# PhatStats_Slim_Enclosure_2_8_ILI9341_QTP.net
KiCad netlist of a schematic drawn in EAGLE
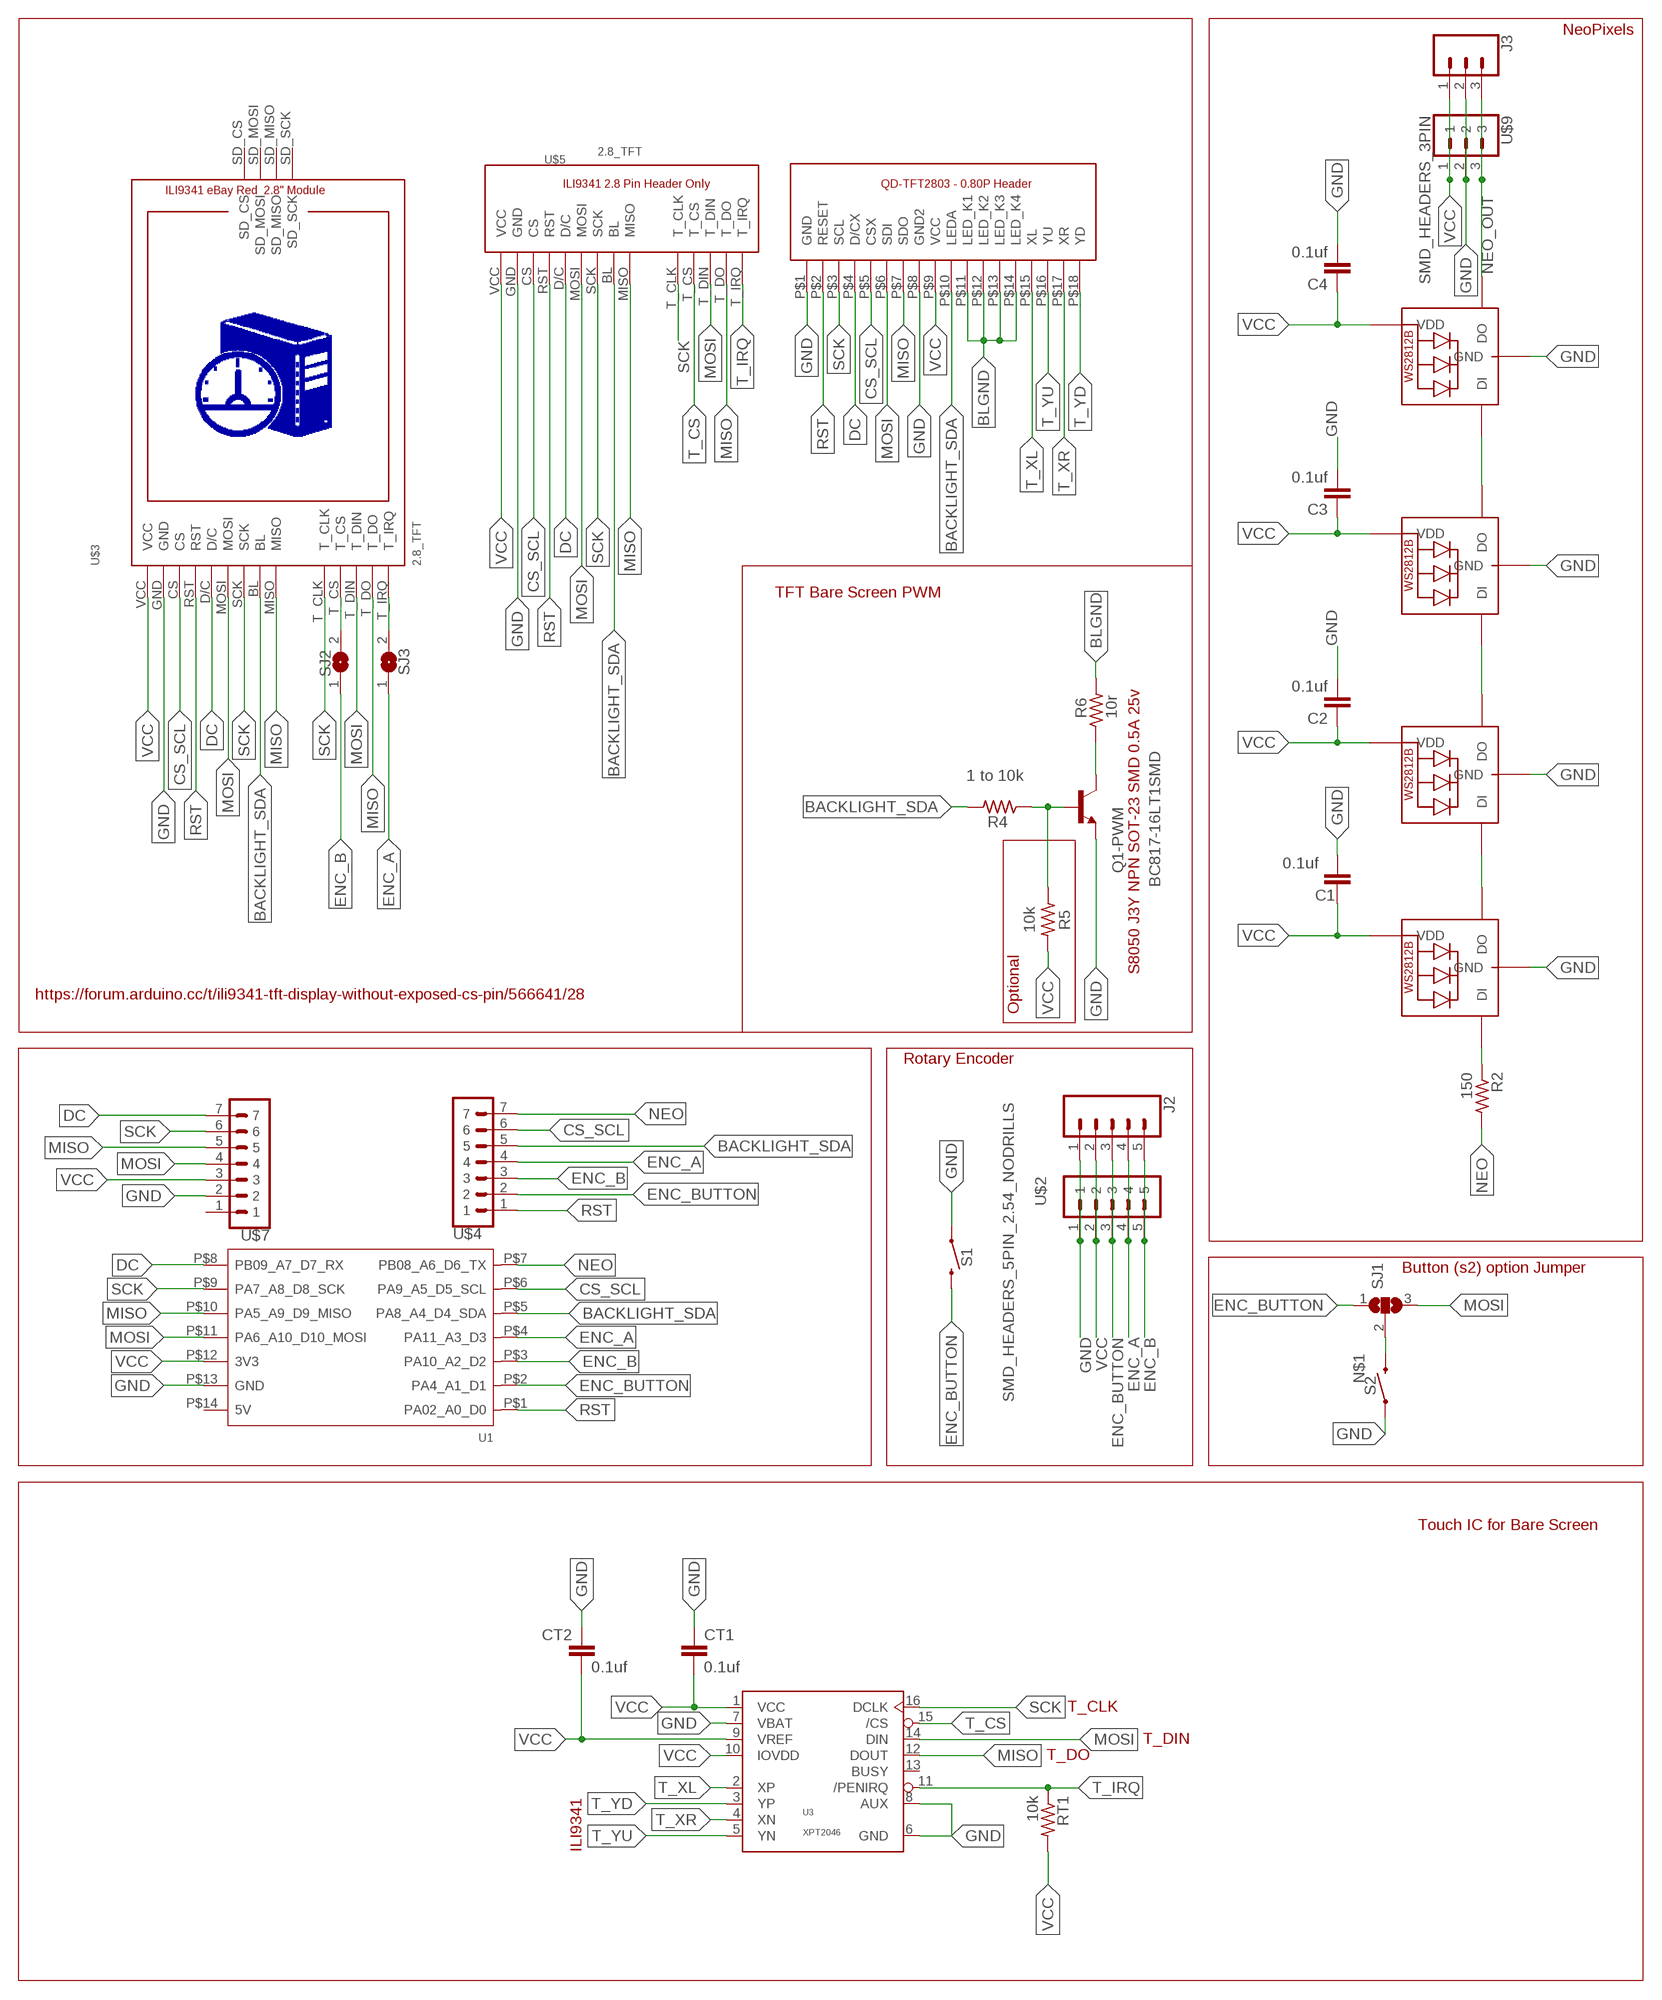
[diagram p0: schematic, sheet 1]

(export (version "E")
  (design (tool "Eeschema 10.0.6"))
  (components
    (comp (ref "0")
      (value "ILI9341-2.8")
      (footprint "eagle-import:ILI9341-2.8")
      (libsource (lib "eagle-import") (part "ILI9341-2.8"))
    )
    (comp (ref "C1")
      (value "0.1uf")
      (footprint "eagle-import:C1206")
      (libsource (lib "eagle-import") (part "C-EUC1206"))
    )
    (comp (ref "C2")
      (value "0.1uf")
      (footprint "eagle-import:C1206")
      (libsource (lib "eagle-import") (part "C-EUC1206"))
    )
    (comp (ref "C3")
      (value "0.1uf")
      (footprint "eagle-import:C1206")
      (libsource (lib "eagle-import") (part "C-EUC1206"))
    )
    (comp (ref "C4")
      (value "0.1uf")
      (footprint "eagle-import:C1206")
      (libsource (lib "eagle-import") (part "C-EUC1206"))
    )
    (comp (ref "CT1")
      (value "0.1uf")
      (footprint "eagle-import:C1206")
      (libsource (lib "eagle-import") (part "C-EUC1206"))
    )
    (comp (ref "CT2")
      (value "0.1uf")
      (footprint "eagle-import:C1206")
      (libsource (lib "eagle-import") (part "C-EUC1206"))
    )
    (comp (ref "J2")
      (value "CONN_05")
      (footprint "eagle-import:1X05")
      (libsource (lib "eagle-import") (part "CONN_05"))
    )
    (comp (ref "J3")
      (value "455-1750-1-ND")
      (footprint "eagle-import:1X03")
      (libsource (lib "eagle-import") (part "CONN_03"))
    )
    (comp (ref "NEO0")
      (value "WS2812B5050")
      (footprint "eagle-import:WS2812B")
      (libsource (lib "eagle-import") (part "WS2812B5050"))
    )
    (comp (ref "NEO1")
      (value "WS2812B5050")
      (footprint "eagle-import:WS2812B")
      (libsource (lib "eagle-import") (part "WS2812B5050"))
    )
    (comp (ref "NEO2")
      (value "WS2812B5050")
      (footprint "eagle-import:WS2812B")
      (libsource (lib "eagle-import") (part "WS2812B5050"))
    )
    (comp (ref "NEO3")
      (value "WS2812B5050")
      (footprint "eagle-import:WS2812B")
      (libsource (lib "eagle-import") (part "WS2812B5050"))
    )
    (comp (ref "Q1-PWM")
      (value "BC817-16LT1SMD")
      (footprint "eagle-import:SOT23-BEC")
      (libsource (lib "eagle-import") (part "BC817SMD-16LT1"))
    )
    (comp (ref "R2")
      (value "150")
      (footprint "eagle-import:M1206")
      (libsource (lib "eagle-import") (part "R-US_M1206"))
    )
    (comp (ref "R4")
      (value "1 to 10k")
      (footprint "eagle-import:M1206")
      (libsource (lib "eagle-import") (part "R-US_M1206"))
    )
    (comp (ref "R5")
      (value "10k")
      (footprint "eagle-import:M1206")
      (libsource (lib "eagle-import") (part "R-US_M1206"))
    )
    (comp (ref "R6")
      (value "10r")
      (footprint "eagle-import:M1206")
      (libsource (lib "eagle-import") (part "R-US_M1206"))
    )
    (comp (ref "RT1")
      (value "10k")
      (footprint "eagle-import:M1206")
      (libsource (lib "eagle-import") (part "R-US_M1206"))
    )
    (comp (ref "S1")
      (value "MOMENTARY-SWITCH-SPST-SMD-6.2MM-TALL")
      (footprint "eagle-import:TACTILE_SWITCH_SMD_6.2MM_TALL")
      (libsource (lib "eagle-import") (part "MOMENTARY-SWITCH-SPST-SMD-6.2MM-TALL"))
    )
    (comp (ref "S2")
      (value "MOMENTARY-SWITCH-SPST-SMD-6.2MM-TALL")
      (footprint "eagle-import:TACTILE_SWITCH_SMD_6.2MM_TALL")
      (libsource (lib "eagle-import") (part "MOMENTARY-SWITCH-SPST-SMD-6.2MM-TALL"))
    )
    (comp (ref "SJ1")
      (value "SJ2W")
      (footprint "eagle-import:SJ_2")
      (libsource (lib "eagle-import") (part "SJ2W"))
    )
    (comp (ref "SJ2") (value "SJ") (footprint "eagle-import:SJ") (libsource (lib "eagle-import") (part "SJ")))
    (comp (ref "SJ3") (value "SJ") (footprint "eagle-import:SJ") (libsource (lib "eagle-import") (part "SJ")))
    (comp (ref "U$2")
      (value "SMD_HEADERS_5PIN_2.54_NODRILLS")
      (footprint "eagle-import:SMD_HEADERS_5PIN")
      (libsource (lib "eagle-import") (part "SMD_HEADERS_5PIN_2.54_NODRILLS"))
    )
    (comp (ref "U$3")
      (value "2.8_TFT")
      (footprint "eagle-import:2.8_TFT")
      (libsource (lib "eagle-import") (part "2.8_TFT"))
    )
    (comp (ref "U$4")
      (value "SMD_HEADERS_7PIN_2.54_NODRILLS")
      (footprint "eagle-import:SMD_HEADERS_7PIN")
      (libsource (lib "eagle-import") (part "SMD_HEADERS_7PIN_2.54_NODRILLS"))
    )
    (comp (ref "U$5")
      (value "2.8_TFT")
      (footprint "eagle-import:2.8_TFT")
      (libsource (lib "eagle-import") (part "TML_ili9341-2.8_tft-display_PinHeader only_2.8_TFT"))
    )
    (comp (ref "U$7")
      (value "SMD_HEADERS_7PIN_2.54_NODRILLS")
      (footprint "eagle-import:SMD_HEADERS_7PIN")
      (libsource (lib "eagle-import") (part "SMD_HEADERS_7PIN_2.54_NODRILLS"))
    )
    (comp (ref "U$9")
      (value "SMD_HEADERS_3PIN")
      (footprint "eagle-import:SMD_HEADERS_3PIN")
      (libsource (lib "eagle-import") (part "SMD_HEADERS_3PIN"))
    )
    (comp (ref "U1")
      (value "MOUDLE-SEEEDUINO-XIAO")
      (footprint "eagle-import:MOUDLE14P-2.54-21X17.8MM")
      (libsource (lib "eagle-import") (part "MOUDLE-SEEEDUINO-XIAO"))
    )
    (comp (ref "U3")
      (value "XPT2046")
      (footprint "eagle-import:TSSOP-16")
      (fields (field (name "MF") "Xptek"))
      (libsource (lib "eagle-import") (part "XPT2046"))
    )
  )
  (nets
    (net (code "1") (name "/N$1") (class "Default")
      (node (ref "S2") (pin "B2") (pinfunction "2_B2") (pintype "passive"))
      (node (ref "SJ1") (pin "2") (pinfunction "2_2") (pintype "passive"))
    )
    (net (code "2") (name "/NEO_OUT") (class "Default")
      (node (ref "J3") (pin "3") (pinfunction "3_3") (pintype "passive"))
      (node (ref "NEO3") (pin "2-DOUT") (pinfunction "DO_2-DOUT") (pintype "output"))
      (node (ref "U$9") (pin "3") (pinfunction "3_3") (pintype "passive"))
    )
    (net (code "3") (name "BACKLIGHT_SDA") (class "Default")
      (node (ref "0") (pin "P$10") (pinfunction "LEDA_P$10") (pintype "bidirectional"))
      (node (ref "R4") (pin "2") (pinfunction "2_2") (pintype "passive"))
      (node (ref "U$3") (pin "BL") (pinfunction "BL_BL") (pintype "bidirectional"))
      (node (ref "U$4") (pin "5") (pinfunction "5_5") (pintype "passive"))
      (node (ref "U$5") (pin "BL") (pinfunction "BL_BL") (pintype "bidirectional"))
      (node (ref "U1") (pin "P$5") (pinfunction "PA8_A4_D4_SDA_P$5") (pintype "bidirectional"))
    )
    (net (code "4") (name "BLGND") (class "Default")
      (node (ref "0") (pin "P$11") (pinfunction "LED_K1_P$11") (pintype "bidirectional"))
      (node (ref "0") (pin "P$12") (pinfunction "LED_K2_P$12") (pintype "bidirectional"))
      (node (ref "0") (pin "P$13") (pinfunction "LED_K3_P$13") (pintype "bidirectional"))
      (node (ref "0") (pin "P$14") (pinfunction "LED_K4_P$14") (pintype "bidirectional"))
      (node (ref "R6") (pin "2") (pinfunction "2_2") (pintype "passive"))
    )
    (net (code "5") (name "CS_SCL") (class "Default")
      (node (ref "0") (pin "P$5") (pinfunction "CSX_P$5") (pintype "bidirectional"))
      (node (ref "U$3") (pin "CS") (pinfunction "CS_CS") (pintype "bidirectional"))
      (node (ref "U$4") (pin "6") (pinfunction "6_6") (pintype "passive"))
      (node (ref "U$5") (pin "CS") (pinfunction "CS_CS") (pintype "bidirectional"))
      (node (ref "U1") (pin "P$6") (pinfunction "PA9_A5_D5_SCL_P$6") (pintype "bidirectional"))
    )
    (net (code "6") (name "DC") (class "Default")
      (node (ref "0") (pin "P$4") (pinfunction "D/CX_P$4") (pintype "bidirectional"))
      (node (ref "U$3") (pin "D/C") (pinfunction "D/C_D/C") (pintype "bidirectional"))
      (node (ref "U$5") (pin "D/C") (pinfunction "D/C_D/C") (pintype "bidirectional"))
      (node (ref "U$7") (pin "7") (pinfunction "7_7") (pintype "passive"))
      (node (ref "U1") (pin "P$8") (pinfunction "PB09_A7_D7_RX_P$8") (pintype "bidirectional"))
    )
    (net (code "7") (name "ENC_A") (class "Default")
      (node (ref "J2") (pin "4") (pinfunction "4_4") (pintype "passive"))
      (node (ref "SJ3") (pin "1") (pinfunction "1_1") (pintype "passive"))
      (node (ref "U$2") (pin "4") (pinfunction "4_4") (pintype "passive"))
      (node (ref "U$4") (pin "4") (pinfunction "4_4") (pintype "passive"))
      (node (ref "U1") (pin "P$4") (pinfunction "PA11_A3_D3_P$4") (pintype "bidirectional"))
    )
    (net (code "8") (name "ENC_B") (class "Default")
      (node (ref "J2") (pin "5") (pinfunction "5_5") (pintype "passive"))
      (node (ref "SJ2") (pin "1") (pinfunction "1_1") (pintype "passive"))
      (node (ref "U$2") (pin "5") (pinfunction "5_5") (pintype "passive"))
      (node (ref "U$4") (pin "3") (pinfunction "3_3") (pintype "passive"))
      (node (ref "U1") (pin "P$3") (pinfunction "PA10_A2_D2_P$3") (pintype "bidirectional"))
    )
    (net (code "9") (name "ENC_BUTTON") (class "Default")
      (node (ref "J2") (pin "3") (pinfunction "3_3") (pintype "passive"))
      (node (ref "S1") (pin "B2") (pinfunction "2_B2") (pintype "passive"))
      (node (ref "SJ1") (pin "1") (pinfunction "1_1") (pintype "passive"))
      (node (ref "U$2") (pin "3") (pinfunction "3_3") (pintype "passive"))
      (node (ref "U$4") (pin "2") (pinfunction "2_2") (pintype "passive"))
      (node (ref "U1") (pin "P$2") (pinfunction "PA4_A1_D1_P$2") (pintype "bidirectional"))
    )
    (net (code "10") (name "GND") (class "Default")
      (node (ref "0") (pin "P$1") (pinfunction "GND_P$1") (pintype "bidirectional"))
      (node (ref "0") (pin "P$8") (pinfunction "GND2_P$8") (pintype "bidirectional"))
      (node (ref "C1") (pin "1") (pinfunction "1_1") (pintype "passive"))
      (node (ref "C2") (pin "2") (pinfunction "2_2") (pintype "passive"))
      (node (ref "C3") (pin "2") (pinfunction "2_2") (pintype "passive"))
      (node (ref "C4") (pin "2") (pinfunction "2_2") (pintype "passive"))
      (node (ref "CT1") (pin "1") (pinfunction "1_1") (pintype "passive"))
      (node (ref "CT2") (pin "1") (pinfunction "1_1") (pintype "passive"))
      (node (ref "J2") (pin "1") (pinfunction "1_1") (pintype "passive"))
      (node (ref "J3") (pin "2") (pinfunction "2_2") (pintype "passive"))
      (node (ref "NEO0") (pin "3-GND") (pinfunction "GND_3-GND") (pintype "power_in"))
      (node (ref "NEO1") (pin "3-GND") (pinfunction "GND_3-GND") (pintype "power_in"))
      (node (ref "NEO2") (pin "3-GND") (pinfunction "GND_3-GND") (pintype "power_in"))
      (node (ref "NEO3") (pin "3-GND") (pinfunction "GND_3-GND") (pintype "power_in"))
      (node (ref "Q1-PWM") (pin "E") (pinfunction "E_E") (pintype "passive"))
      (node (ref "S1") (pin "A2") (pinfunction "1_A2") (pintype "passive"))
      (node (ref "S2") (pin "A2") (pinfunction "1_A2") (pintype "passive"))
      (node (ref "U$2") (pin "1") (pinfunction "1_1") (pintype "passive"))
      (node (ref "U$3") (pin "GND") (pinfunction "GND_GND") (pintype "bidirectional"))
      (node (ref "U$5") (pin "GND") (pinfunction "GND_GND") (pintype "bidirectional"))
      (node (ref "U$7") (pin "2") (pinfunction "2_2") (pintype "passive"))
      (node (ref "U$9") (pin "2") (pinfunction "2_2") (pintype "passive"))
      (node (ref "U1") (pin "P$13") (pinfunction "GND_P$13") (pintype "bidirectional"))
      (node (ref "U3") (pin "6") (pinfunction "GND_6") (pintype "power_in"))
      (node (ref "U3") (pin "7") (pinfunction "VBAT_7") (pintype "input"))
      (node (ref "U3") (pin "8") (pinfunction "AUX_8") (pintype "input"))
    )
    (net (code "11") (name "MISO") (class "Default")
      (node (ref "0") (pin "P$7") (pinfunction "SDO_P$7") (pintype "bidirectional"))
      (node (ref "U$3") (pin "MISO") (pinfunction "MISO_MISO") (pintype "bidirectional"))
      (node (ref "U$3") (pin "T_DO") (pinfunction "T_DO_T_DO") (pintype "bidirectional"))
      (node (ref "U$5") (pin "MISO") (pinfunction "MISO_MISO") (pintype "bidirectional"))
      (node (ref "U$5") (pin "T_DO") (pinfunction "T_DO_T_DO") (pintype "bidirectional"))
      (node (ref "U$7") (pin "5") (pinfunction "5_5") (pintype "passive"))
      (node (ref "U1") (pin "P$10") (pinfunction "PA5_A9_D9_MISO_P$10") (pintype "bidirectional"))
      (node (ref "U3") (pin "12") (pinfunction "DOUT_12") (pintype "output"))
    )
    (net (code "12") (name "MOSI") (class "Default")
      (node (ref "0") (pin "P$6") (pinfunction "SDI_P$6") (pintype "bidirectional"))
      (node (ref "SJ1") (pin "3") (pinfunction "3_3") (pintype "passive"))
      (node (ref "U$3") (pin "MOSI") (pinfunction "MOSI_MOSI") (pintype "bidirectional"))
      (node (ref "U$3") (pin "T_DIN") (pinfunction "T_DIN_T_DIN") (pintype "bidirectional"))
      (node (ref "U$5") (pin "MOSI") (pinfunction "MOSI_MOSI") (pintype "bidirectional"))
      (node (ref "U$5") (pin "T_DIN") (pinfunction "T_DIN_T_DIN") (pintype "bidirectional"))
      (node (ref "U$7") (pin "4") (pinfunction "4_4") (pintype "passive"))
      (node (ref "U1") (pin "P$11") (pinfunction "PA6_A10_D10_MOSI_P$11") (pintype "bidirectional"))
      (node (ref "U3") (pin "14") (pinfunction "DIN_14") (pintype "input"))
    )
    (net (code "13") (name "NEO") (class "Default")
      (node (ref "R2") (pin "2") (pinfunction "2_2") (pintype "passive"))
      (node (ref "U$4") (pin "7") (pinfunction "7_7") (pintype "passive"))
      (node (ref "U1") (pin "P$7") (pinfunction "PB08_A6_D6_TX_P$7") (pintype "bidirectional"))
    )
    (net (code "14") (name "Net-(NEO0-DI)") (class "Default")
      (node (ref "NEO0") (pin "4-DIN") (pinfunction "DI_4-DIN") (pintype "input"))
      (node (ref "R2") (pin "1") (pinfunction "1_1") (pintype "passive"))
    )
    (net (code "15") (name "Net-(NEO0-DO)") (class "Default")
      (node (ref "NEO0") (pin "2-DOUT") (pinfunction "DO_2-DOUT") (pintype "output"))
      (node (ref "NEO1") (pin "4-DIN") (pinfunction "DI_4-DIN") (pintype "input"))
    )
    (net (code "16") (name "Net-(NEO1-DO)") (class "Default")
      (node (ref "NEO1") (pin "2-DOUT") (pinfunction "DO_2-DOUT") (pintype "output"))
      (node (ref "NEO2") (pin "4-DIN") (pinfunction "DI_4-DIN") (pintype "input"))
    )
    (net (code "17") (name "Net-(NEO2-DO)") (class "Default")
      (node (ref "NEO2") (pin "2-DOUT") (pinfunction "DO_2-DOUT") (pintype "output"))
      (node (ref "NEO3") (pin "4-DIN") (pinfunction "DI_4-DIN") (pintype "input"))
    )
    (net (code "18") (name "Net-(Q1-PWM-PadB)") (class "Default")
      (node (ref "Q1-PWM") (pin "B") (pinfunction "B_B") (pintype "passive"))
      (node (ref "R4") (pin "1") (pinfunction "1_1") (pintype "passive"))
      (node (ref "R5") (pin "1") (pinfunction "1_1") (pintype "passive"))
    )
    (net (code "19") (name "Net-(Q1-PWM-PadC)") (class "Default")
      (node (ref "Q1-PWM") (pin "C") (pinfunction "C_C") (pintype "passive"))
      (node (ref "R6") (pin "1") (pinfunction "1_1") (pintype "passive"))
    )
    (net (code "20") (name "RST") (class "Default")
      (node (ref "0") (pin "P$2") (pinfunction "RESET_P$2") (pintype "bidirectional"))
      (node (ref "U$3") (pin "RST") (pinfunction "RST_RST") (pintype "bidirectional"))
      (node (ref "U$4") (pin "1") (pinfunction "1_1") (pintype "passive"))
      (node (ref "U$5") (pin "RST") (pinfunction "RST_RST") (pintype "bidirectional"))
      (node (ref "U1") (pin "P$1") (pinfunction "PA02_A0_D0_P$1") (pintype "bidirectional"))
    )
    (net (code "21") (name "SCK") (class "Default")
      (node (ref "0") (pin "P$3") (pinfunction "SCL_P$3") (pintype "bidirectional"))
      (node (ref "U$3") (pin "SCK") (pinfunction "SCK_SCK") (pintype "bidirectional"))
      (node (ref "U$3") (pin "T_CLK") (pinfunction "T_CLK_T_CLK") (pintype "bidirectional"))
      (node (ref "U$5") (pin "SCK") (pinfunction "SCK_SCK") (pintype "bidirectional"))
      (node (ref "U$5") (pin "T_CLK") (pinfunction "T_CLK_T_CLK") (pintype "bidirectional"))
      (node (ref "U$7") (pin "6") (pinfunction "6_6") (pintype "passive"))
      (node (ref "U1") (pin "P$9") (pinfunction "PA7_A8_D8_SCK_P$9") (pintype "bidirectional"))
      (node (ref "U3") (pin "16") (pinfunction "DCLK_16") (pintype "input"))
    )
    (net (code "22") (name "T_CS") (class "Default")
      (node (ref "SJ2") (pin "2") (pinfunction "2_2") (pintype "passive"))
      (node (ref "U$3") (pin "T_CS") (pinfunction "T_CS_T_CS") (pintype "bidirectional"))
      (node (ref "U$5") (pin "T_CS") (pinfunction "T_CS_T_CS") (pintype "bidirectional"))
      (node (ref "U3") (pin "15") (pinfunction "/CS_15") (pintype "input"))
    )
    (net (code "23") (name "T_IRQ") (class "Default")
      (node (ref "RT1") (pin "1") (pinfunction "1_1") (pintype "passive"))
      (node (ref "SJ3") (pin "2") (pinfunction "2_2") (pintype "passive"))
      (node (ref "U$3") (pin "T_IRQ") (pinfunction "T_IRQ_T_IRQ") (pintype "bidirectional"))
      (node (ref "U$5") (pin "T_IRQ") (pinfunction "T_IRQ_T_IRQ") (pintype "bidirectional"))
      (node (ref "U3") (pin "11") (pinfunction "/PENIRQ_11") (pintype "output"))
    )
    (net (code "24") (name "T_XL") (class "Default")
      (node (ref "0") (pin "P$15") (pinfunction "XL_P$15") (pintype "bidirectional"))
      (node (ref "U3") (pin "2") (pinfunction "XP_2") (pintype "input"))
    )
    (net (code "25") (name "T_XR") (class "Default")
      (node (ref "0") (pin "P$17") (pinfunction "XR_P$17") (pintype "bidirectional"))
      (node (ref "U3") (pin "4") (pinfunction "XN_4") (pintype "input"))
    )
    (net (code "26") (name "T_YD") (class "Default")
      (node (ref "0") (pin "P$18") (pinfunction "YD_P$18") (pintype "bidirectional"))
      (node (ref "U3") (pin "3") (pinfunction "YP_3") (pintype "input"))
    )
    (net (code "27") (name "T_YU") (class "Default")
      (node (ref "0") (pin "P$16") (pinfunction "YU_P$16") (pintype "bidirectional"))
      (node (ref "U3") (pin "5") (pinfunction "YN_5") (pintype "input"))
    )
    (net (code "28") (name "VCC") (class "Default")
      (node (ref "0") (pin "P$9") (pinfunction "VCC_P$9") (pintype "bidirectional"))
      (node (ref "C1") (pin "2") (pinfunction "2_2") (pintype "passive"))
      (node (ref "C2") (pin "1") (pinfunction "1_1") (pintype "passive"))
      (node (ref "C3") (pin "1") (pinfunction "1_1") (pintype "passive"))
      (node (ref "C4") (pin "1") (pinfunction "1_1") (pintype "passive"))
      (node (ref "CT1") (pin "2") (pinfunction "2_2") (pintype "passive"))
      (node (ref "CT2") (pin "2") (pinfunction "2_2") (pintype "passive"))
      (node (ref "J2") (pin "2") (pinfunction "2_2") (pintype "passive"))
      (node (ref "J3") (pin "1") (pinfunction "1_1") (pintype "passive"))
      (node (ref "NEO0") (pin "1-VDD") (pinfunction "VDD_1-VDD") (pintype "power_in"))
      (node (ref "NEO1") (pin "1-VDD") (pinfunction "VDD_1-VDD") (pintype "power_in"))
      (node (ref "NEO2") (pin "1-VDD") (pinfunction "VDD_1-VDD") (pintype "power_in"))
      (node (ref "NEO3") (pin "1-VDD") (pinfunction "VDD_1-VDD") (pintype "power_in"))
      (node (ref "R5") (pin "2") (pinfunction "2_2") (pintype "passive"))
      (node (ref "RT1") (pin "2") (pinfunction "2_2") (pintype "passive"))
      (node (ref "U$2") (pin "2") (pinfunction "2_2") (pintype "passive"))
      (node (ref "U$3") (pin "VCC") (pinfunction "VCC_VCC") (pintype "bidirectional"))
      (node (ref "U$5") (pin "VCC") (pinfunction "VCC_VCC") (pintype "bidirectional"))
      (node (ref "U$7") (pin "3") (pinfunction "3_3") (pintype "passive"))
      (node (ref "U$9") (pin "1") (pinfunction "1_1") (pintype "passive"))
      (node (ref "U1") (pin "P$12") (pinfunction "3V3_P$12") (pintype "bidirectional"))
      (node (ref "U3") (pin "1") (pinfunction "VCC_1") (pintype "power_in"))
      (node (ref "U3") (pin "10") (pinfunction "IOVDD_10") (pintype "power_in"))
      (node (ref "U3") (pin "9") (pinfunction "VREF_9") (pintype "input"))
    )
    (net (code "29") (name "unconnected-(U$3-PadSD_CS)") (class "Default")
      (node (ref "U$3") (pin "SD_CS") (pinfunction "SD_CS_SD_CS") (pintype "bidirectional"))
    )
    (net (code "30") (name "unconnected-(U$3-PadSD_MISO)") (class "Default")
      (node (ref "U$3") (pin "SD_MISO") (pinfunction "SD_MISO_SD_MISO") (pintype "bidirectional"))
    )
    (net (code "31") (name "unconnected-(U$3-PadSD_MOSI)") (class "Default")
      (node (ref "U$3") (pin "SD_MOSI") (pinfunction "SD_MOSI_SD_MOSI") (pintype "bidirectional"))
    )
    (net (code "32") (name "unconnected-(U$3-PadSD_SCK)") (class "Default")
      (node (ref "U$3") (pin "SD_SCK") (pinfunction "SD_SCK_SD_SCK") (pintype "bidirectional"))
    )
    (net (code "33") (name "unconnected-(U$7-Pad1)") (class "Default")
      (node (ref "U$7") (pin "1") (pinfunction "1_1") (pintype "passive"))
    )
    (net (code "34") (name "unconnected-(U1-5V-PadP$14)") (class "Default")
      (node (ref "U1") (pin "P$14") (pinfunction "5V_P$14") (pintype "bidirectional"))
    )
    (net (code "35") (name "unconnected-(U3-BUSY-Pad13)") (class "Default")
      (node (ref "U3") (pin "13") (pinfunction "BUSY_13") (pintype "output"))
    )
  )
)
